# RPiLPC1114FDH28.net
KiCad netlist of a schematic drawn in EAGLE
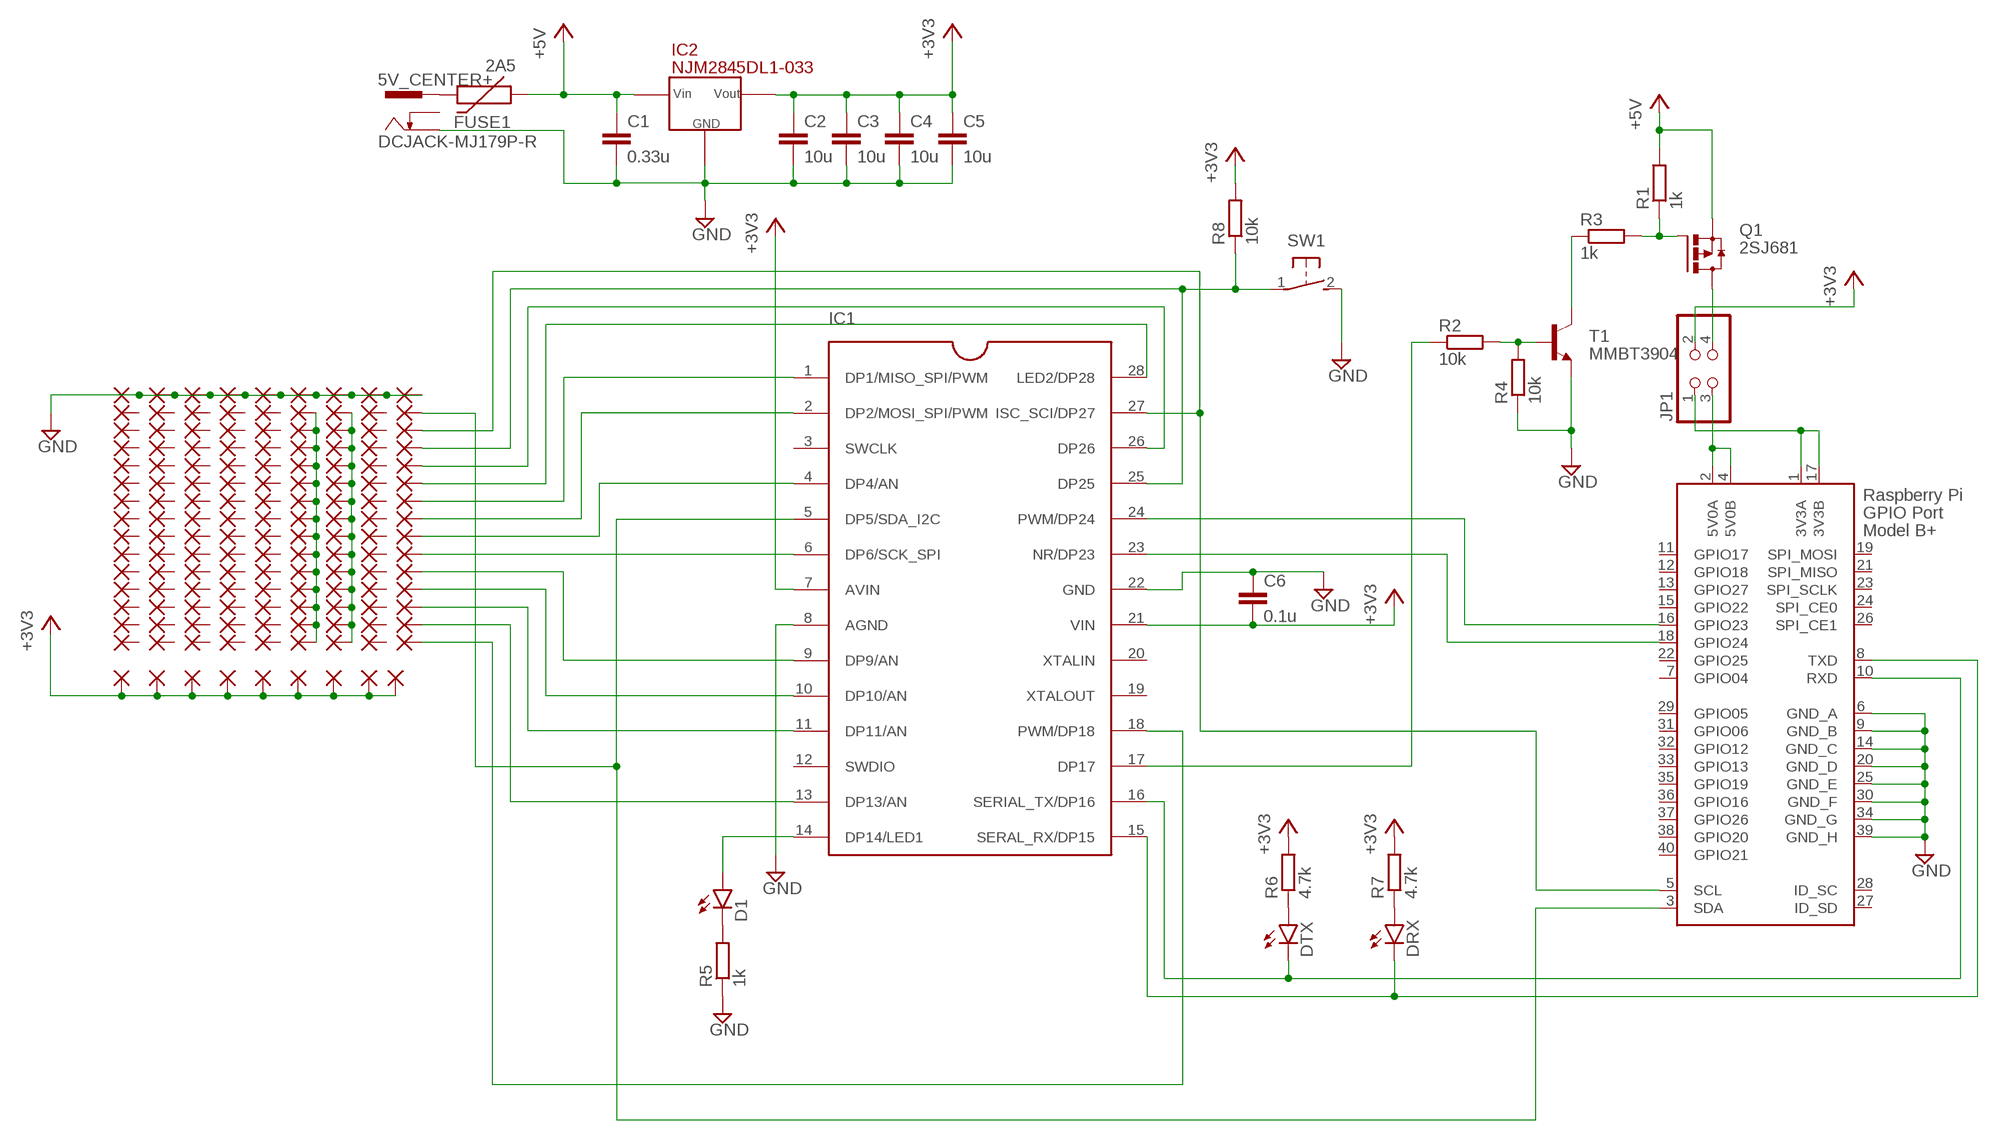
[diagram p0: schematic, sheet 1]

(export (version "E")
  (design (tool "Eeschema 10.0.6"))
  (components
    (comp (ref "5V_CENTER+")
      (value "DCJACK-MJ179P-R")
      (footprint "eagle-import:MJ-179P-R")
      (libsource (lib "eagle-import") (part "DCJACK-MJ179P-R"))
    )
    (comp (ref "C1")
      (value "0.33u")
      (footprint "eagle-import:C0603")
      (libsource (lib "eagle-import") (part "C-EUC0603"))
    )
    (comp (ref "C2")
      (value "10u")
      (footprint "eagle-import:C0805")
      (libsource (lib "eagle-import") (part "C-EUC0805"))
    )
    (comp (ref "C3")
      (value "10u")
      (footprint "eagle-import:C0805")
      (libsource (lib "eagle-import") (part "C-EUC0805"))
    )
    (comp (ref "C4")
      (value "10u")
      (footprint "eagle-import:C0805")
      (libsource (lib "eagle-import") (part "C-EUC0805"))
    )
    (comp (ref "C5")
      (value "10u")
      (footprint "eagle-import:C0805")
      (libsource (lib "eagle-import") (part "C-EUC0805"))
    )
    (comp (ref "C6")
      (value "0.1u")
      (footprint "eagle-import:C0603")
      (libsource (lib "eagle-import") (part "C-EUC0603"))
    )
    (comp (ref "D1")
      (value "LED0603")
      (footprint "eagle-import:LED-0603")
      (libsource (lib "eagle-import") (part "LED0603"))
    )
    (comp (ref "DRX")
      (value "LED0603")
      (footprint "eagle-import:LED-0603")
      (libsource (lib "eagle-import") (part "LED0603"))
    )
    (comp (ref "DTX")
      (value "LED0603")
      (footprint "eagle-import:LED-0603")
      (libsource (lib "eagle-import") (part "LED0603"))
    )
    (comp (ref "FUSE1")
      (value "2A5")
      (footprint "eagle-import:PTC")
      (libsource (lib "eagle-import") (part "PTCPTH"))
    )
    (comp (ref "IC1")
      (value "LPC1114DH28")
      (footprint "eagle-import:TSSOP28")
      (libsource (lib "eagle-import") (part "LPC1114DH28"))
    )
    (comp (ref "IC2")
      (value "NJM2845DL1-033")
      (footprint "eagle-import:TO-252-3")
      (libsource (lib "eagle-import") (part "NJM2845DL1"))
    )
    (comp (ref "JP1")
      (value "PINHD-2X2")
      (footprint "eagle-import:2X02")
      (libsource (lib "eagle-import") (part "PINHD-2X2"))
    )
    (comp (ref "PAD-3V3")
      (value "WIREPAD1,6/0,8")
      (footprint "eagle-import:1,6_0,8")
      (libsource (lib "eagle-import") (part "WIREPAD1,6/0,8"))
    )
    (comp (ref "PAD-DP1")
      (value "WIREPAD1,6/0,8")
      (footprint "eagle-import:1,6_0,8")
      (libsource (lib "eagle-import") (part "WIREPAD1,6/0,8"))
    )
    (comp (ref "PAD-DP2")
      (value "WIREPAD1,6/0,8")
      (footprint "eagle-import:1,6_0,8")
      (libsource (lib "eagle-import") (part "WIREPAD1,6/0,8"))
    )
    (comp (ref "PAD-DP4")
      (value "WIREPAD1,6/0,8")
      (footprint "eagle-import:1,6_0,8")
      (libsource (lib "eagle-import") (part "WIREPAD1,6/0,8"))
    )
    (comp (ref "PAD-DP5/SDA")
      (value "WIREPAD1,6/0,8")
      (footprint "eagle-import:1,6_0,8")
      (libsource (lib "eagle-import") (part "WIREPAD1,6/0,8"))
    )
    (comp (ref "PAD-DP6")
      (value "WIREPAD1,6/0,8")
      (footprint "eagle-import:1,6_0,8")
      (libsource (lib "eagle-import") (part "WIREPAD1,6/0,8"))
    )
    (comp (ref "PAD-DP9")
      (value "WIREPAD1,6/0,8")
      (footprint "eagle-import:1,6_0,8")
      (libsource (lib "eagle-import") (part "WIREPAD1,6/0,8"))
    )
    (comp (ref "PAD-DP10")
      (value "WIREPAD1,6/0,8")
      (footprint "eagle-import:1,6_0,8")
      (libsource (lib "eagle-import") (part "WIREPAD1,6/0,8"))
    )
    (comp (ref "PAD-DP11")
      (value "WIREPAD1,6/0,8")
      (footprint "eagle-import:1,6_0,8")
      (libsource (lib "eagle-import") (part "WIREPAD1,6/0,8"))
    )
    (comp (ref "PAD-DP13")
      (value "WIREPAD1,6/0,8")
      (footprint "eagle-import:1,6_0,8")
      (libsource (lib "eagle-import") (part "WIREPAD1,6/0,8"))
    )
    (comp (ref "PAD-DP18")
      (value "WIREPAD1,6/0,8")
      (footprint "eagle-import:1,6_0,8")
      (libsource (lib "eagle-import") (part "WIREPAD1,6/0,8"))
    )
    (comp (ref "PAD-DP25")
      (value "WIREPAD1,6/0,8")
      (footprint "eagle-import:1,6_0,8")
      (libsource (lib "eagle-import") (part "WIREPAD1,6/0,8"))
    )
    (comp (ref "PAD-DP26")
      (value "WIREPAD1,6/0,8")
      (footprint "eagle-import:1,6_0,8")
      (libsource (lib "eagle-import") (part "WIREPAD1,6/0,8"))
    )
    (comp (ref "PAD-DP27/SCL")
      (value "WIREPAD1,6/0,8")
      (footprint "eagle-import:1,6_0,8")
      (libsource (lib "eagle-import") (part "WIREPAD1,6/0,8"))
    )
    (comp (ref "PAD-DP28")
      (value "WIREPAD1,6/0,8")
      (footprint "eagle-import:1,6_0,8")
      (libsource (lib "eagle-import") (part "WIREPAD1,6/0,8"))
    )
    (comp (ref "PAD1")
      (value "WIREPAD1,6/0,8")
      (footprint "eagle-import:1,6_0,8")
      (libsource (lib "eagle-import") (part "WIREPAD1,6/0,8"))
    )
    (comp (ref "PAD2")
      (value "WIREPAD1,6/0,8")
      (footprint "eagle-import:1,6_0,8")
      (libsource (lib "eagle-import") (part "WIREPAD1,6/0,8"))
    )
    (comp (ref "PAD3")
      (value "WIREPAD1,6/0,8")
      (footprint "eagle-import:1,6_0,8")
      (libsource (lib "eagle-import") (part "WIREPAD1,6/0,8"))
    )
    (comp (ref "PAD4")
      (value "WIREPAD1,6/0,8")
      (footprint "eagle-import:1,6_0,8")
      (libsource (lib "eagle-import") (part "WIREPAD1,6/0,8"))
    )
    (comp (ref "PAD5")
      (value "WIREPAD1,6/0,8")
      (footprint "eagle-import:1,6_0,8")
      (libsource (lib "eagle-import") (part "WIREPAD1,6/0,8"))
    )
    (comp (ref "PAD6")
      (value "WIREPAD1,6/0,8")
      (footprint "eagle-import:1,6_0,8")
      (libsource (lib "eagle-import") (part "WIREPAD1,6/0,8"))
    )
    (comp (ref "PAD7")
      (value "WIREPAD1,6/0,8")
      (footprint "eagle-import:1,6_0,8")
      (libsource (lib "eagle-import") (part "WIREPAD1,6/0,8"))
    )
    (comp (ref "PAD8")
      (value "WIREPAD1,6/0,8")
      (footprint "eagle-import:1,6_0,8")
      (libsource (lib "eagle-import") (part "WIREPAD1,6/0,8"))
    )
    (comp (ref "PAD9")
      (value "WIREPAD1,6/0,8")
      (footprint "eagle-import:1,6_0,8")
      (libsource (lib "eagle-import") (part "WIREPAD1,6/0,8"))
    )
    (comp (ref "PAD10")
      (value "WIREPAD1,6/0,8")
      (footprint "eagle-import:1,6_0,8")
      (libsource (lib "eagle-import") (part "WIREPAD1,6/0,8"))
    )
    (comp (ref "PAD11")
      (value "WIREPAD1,6/0,8")
      (footprint "eagle-import:1,6_0,8")
      (libsource (lib "eagle-import") (part "WIREPAD1,6/0,8"))
    )
    (comp (ref "PAD12")
      (value "WIREPAD1,6/0,8")
      (footprint "eagle-import:1,6_0,8")
      (libsource (lib "eagle-import") (part "WIREPAD1,6/0,8"))
    )
    (comp (ref "PAD13")
      (value "WIREPAD1,6/0,8")
      (footprint "eagle-import:1,6_0,8")
      (libsource (lib "eagle-import") (part "WIREPAD1,6/0,8"))
    )
    (comp (ref "PAD14")
      (value "WIREPAD1,6/0,8")
      (footprint "eagle-import:1,6_0,8")
      (libsource (lib "eagle-import") (part "WIREPAD1,6/0,8"))
    )
    (comp (ref "PAD15")
      (value "WIREPAD1,6/0,8")
      (footprint "eagle-import:1,6_0,8")
      (libsource (lib "eagle-import") (part "WIREPAD1,6/0,8"))
    )
    (comp (ref "PAD16")
      (value "WIREPAD1,6/0,8")
      (footprint "eagle-import:1,6_0,8")
      (libsource (lib "eagle-import") (part "WIREPAD1,6/0,8"))
    )
    (comp (ref "PAD17")
      (value "WIREPAD1,6/0,8")
      (footprint "eagle-import:1,6_0,8")
      (libsource (lib "eagle-import") (part "WIREPAD1,6/0,8"))
    )
    (comp (ref "PAD18")
      (value "WIREPAD1,6/0,8")
      (footprint "eagle-import:1,6_0,8")
      (libsource (lib "eagle-import") (part "WIREPAD1,6/0,8"))
    )
    (comp (ref "PAD19")
      (value "WIREPAD1,6/0,8")
      (footprint "eagle-import:1,6_0,8")
      (libsource (lib "eagle-import") (part "WIREPAD1,6/0,8"))
    )
    (comp (ref "PAD20")
      (value "WIREPAD1,6/0,8")
      (footprint "eagle-import:1,6_0,8")
      (libsource (lib "eagle-import") (part "WIREPAD1,6/0,8"))
    )
    (comp (ref "PAD21")
      (value "WIREPAD1,6/0,8")
      (footprint "eagle-import:1,6_0,8")
      (libsource (lib "eagle-import") (part "WIREPAD1,6/0,8"))
    )
    (comp (ref "PAD22")
      (value "WIREPAD1,6/0,8")
      (footprint "eagle-import:1,6_0,8")
      (libsource (lib "eagle-import") (part "WIREPAD1,6/0,8"))
    )
    (comp (ref "PAD23")
      (value "WIREPAD1,6/0,8")
      (footprint "eagle-import:1,6_0,8")
      (libsource (lib "eagle-import") (part "WIREPAD1,6/0,8"))
    )
    (comp (ref "PAD24")
      (value "WIREPAD1,6/0,8")
      (footprint "eagle-import:1,6_0,8")
      (libsource (lib "eagle-import") (part "WIREPAD1,6/0,8"))
    )
    (comp (ref "PAD25")
      (value "WIREPAD1,6/0,8")
      (footprint "eagle-import:1,6_0,8")
      (libsource (lib "eagle-import") (part "WIREPAD1,6/0,8"))
    )
    (comp (ref "PAD26")
      (value "WIREPAD1,6/0,8")
      (footprint "eagle-import:1,6_0,8")
      (libsource (lib "eagle-import") (part "WIREPAD1,6/0,8"))
    )
    (comp (ref "PAD27")
      (value "WIREPAD1,6/0,8")
      (footprint "eagle-import:1,6_0,8")
      (libsource (lib "eagle-import") (part "WIREPAD1,6/0,8"))
    )
    (comp (ref "PAD28")
      (value "WIREPAD1,6/0,8")
      (footprint "eagle-import:1,6_0,8")
      (libsource (lib "eagle-import") (part "WIREPAD1,6/0,8"))
    )
    (comp (ref "PAD29")
      (value "WIREPAD1,6/0,8")
      (footprint "eagle-import:1,6_0,8")
      (libsource (lib "eagle-import") (part "WIREPAD1,6/0,8"))
    )
    (comp (ref "PAD30")
      (value "WIREPAD1,6/0,8")
      (footprint "eagle-import:1,6_0,8")
      (libsource (lib "eagle-import") (part "WIREPAD1,6/0,8"))
    )
    (comp (ref "PAD31")
      (value "WIREPAD1,6/0,8")
      (footprint "eagle-import:1,6_0,8")
      (libsource (lib "eagle-import") (part "WIREPAD1,6/0,8"))
    )
    (comp (ref "PAD32")
      (value "WIREPAD1,6/0,8")
      (footprint "eagle-import:1,6_0,8")
      (libsource (lib "eagle-import") (part "WIREPAD1,6/0,8"))
    )
    (comp (ref "PAD33")
      (value "WIREPAD1,6/0,8")
      (footprint "eagle-import:1,6_0,8")
      (libsource (lib "eagle-import") (part "WIREPAD1,6/0,8"))
    )
    (comp (ref "PAD34")
      (value "WIREPAD1,6/0,8")
      (footprint "eagle-import:1,6_0,8")
      (libsource (lib "eagle-import") (part "WIREPAD1,6/0,8"))
    )
    (comp (ref "PAD35")
      (value "WIREPAD1,6/0,8")
      (footprint "eagle-import:1,6_0,8")
      (libsource (lib "eagle-import") (part "WIREPAD1,6/0,8"))
    )
    (comp (ref "PAD36")
      (value "WIREPAD1,6/0,8")
      (footprint "eagle-import:1,6_0,8")
      (libsource (lib "eagle-import") (part "WIREPAD1,6/0,8"))
    )
    (comp (ref "PAD37")
      (value "WIREPAD1,6/0,8")
      (footprint "eagle-import:1,6_0,8")
      (libsource (lib "eagle-import") (part "WIREPAD1,6/0,8"))
    )
    (comp (ref "PAD38")
      (value "WIREPAD1,6/0,8")
      (footprint "eagle-import:1,6_0,8")
      (libsource (lib "eagle-import") (part "WIREPAD1,6/0,8"))
    )
    (comp (ref "PAD39")
      (value "WIREPAD1,6/0,8")
      (footprint "eagle-import:1,6_0,8")
      (libsource (lib "eagle-import") (part "WIREPAD1,6/0,8"))
    )
    (comp (ref "PAD40")
      (value "WIREPAD1,6/0,8")
      (footprint "eagle-import:1,6_0,8")
      (libsource (lib "eagle-import") (part "WIREPAD1,6/0,8"))
    )
    (comp (ref "PAD41")
      (value "WIREPAD1,6/0,8")
      (footprint "eagle-import:1,6_0,8")
      (libsource (lib "eagle-import") (part "WIREPAD1,6/0,8"))
    )
    (comp (ref "PAD42")
      (value "WIREPAD1,6/0,8")
      (footprint "eagle-import:1,6_0,8")
      (libsource (lib "eagle-import") (part "WIREPAD1,6/0,8"))
    )
    (comp (ref "PAD43")
      (value "WIREPAD1,6/0,8")
      (footprint "eagle-import:1,6_0,8")
      (libsource (lib "eagle-import") (part "WIREPAD1,6/0,8"))
    )
    (comp (ref "PAD44")
      (value "WIREPAD1,6/0,8")
      (footprint "eagle-import:1,6_0,8")
      (libsource (lib "eagle-import") (part "WIREPAD1,6/0,8"))
    )
    (comp (ref "PAD45")
      (value "WIREPAD1,6/0,8")
      (footprint "eagle-import:1,6_0,8")
      (libsource (lib "eagle-import") (part "WIREPAD1,6/0,8"))
    )
    (comp (ref "PAD46")
      (value "WIREPAD1,6/0,8")
      (footprint "eagle-import:1,6_0,8")
      (libsource (lib "eagle-import") (part "WIREPAD1,6/0,8"))
    )
    (comp (ref "PAD47")
      (value "WIREPAD1,6/0,8")
      (footprint "eagle-import:1,6_0,8")
      (libsource (lib "eagle-import") (part "WIREPAD1,6/0,8"))
    )
    (comp (ref "PAD48")
      (value "WIREPAD1,6/0,8")
      (footprint "eagle-import:1,6_0,8")
      (libsource (lib "eagle-import") (part "WIREPAD1,6/0,8"))
    )
    (comp (ref "PAD49")
      (value "WIREPAD1,6/0,8")
      (footprint "eagle-import:1,6_0,8")
      (libsource (lib "eagle-import") (part "WIREPAD1,6/0,8"))
    )
    (comp (ref "PAD50")
      (value "WIREPAD1,6/0,8")
      (footprint "eagle-import:1,6_0,8")
      (libsource (lib "eagle-import") (part "WIREPAD1,6/0,8"))
    )
    (comp (ref "PAD51")
      (value "WIREPAD1,6/0,8")
      (footprint "eagle-import:1,6_0,8")
      (libsource (lib "eagle-import") (part "WIREPAD1,6/0,8"))
    )
    (comp (ref "PAD53")
      (value "WIREPAD1,6/0,8")
      (footprint "eagle-import:1,6_0,8")
      (libsource (lib "eagle-import") (part "WIREPAD1,6/0,8"))
    )
    (comp (ref "PAD54")
      (value "WIREPAD1,6/0,8")
      (footprint "eagle-import:1,6_0,8")
      (libsource (lib "eagle-import") (part "WIREPAD1,6/0,8"))
    )
    (comp (ref "PAD55")
      (value "WIREPAD1,6/0,8")
      (footprint "eagle-import:1,6_0,8")
      (libsource (lib "eagle-import") (part "WIREPAD1,6/0,8"))
    )
    (comp (ref "PAD56")
      (value "WIREPAD1,6/0,8")
      (footprint "eagle-import:1,6_0,8")
      (libsource (lib "eagle-import") (part "WIREPAD1,6/0,8"))
    )
    (comp (ref "PAD57")
      (value "WIREPAD1,6/0,8")
      (footprint "eagle-import:1,6_0,8")
      (libsource (lib "eagle-import") (part "WIREPAD1,6/0,8"))
    )
    (comp (ref "PAD58")
      (value "WIREPAD1,6/0,8")
      (footprint "eagle-import:1,6_0,8")
      (libsource (lib "eagle-import") (part "WIREPAD1,6/0,8"))
    )
    (comp (ref "PAD59")
      (value "WIREPAD1,6/0,8")
      (footprint "eagle-import:1,6_0,8")
      (libsource (lib "eagle-import") (part "WIREPAD1,6/0,8"))
    )
    (comp (ref "PAD60")
      (value "WIREPAD1,6/0,8")
      (footprint "eagle-import:1,6_0,8")
      (libsource (lib "eagle-import") (part "WIREPAD1,6/0,8"))
    )
    (comp (ref "PAD61")
      (value "WIREPAD1,6/0,8")
      (footprint "eagle-import:1,6_0,8")
      (libsource (lib "eagle-import") (part "WIREPAD1,6/0,8"))
    )
    (comp (ref "PAD62")
      (value "WIREPAD1,6/0,8")
      (footprint "eagle-import:1,6_0,8")
      (libsource (lib "eagle-import") (part "WIREPAD1,6/0,8"))
    )
    (comp (ref "PAD63")
      (value "WIREPAD1,6/0,8")
      (footprint "eagle-import:1,6_0,8")
      (libsource (lib "eagle-import") (part "WIREPAD1,6/0,8"))
    )
    (comp (ref "PAD64")
      (value "WIREPAD1,6/0,8")
      (footprint "eagle-import:1,6_0,8")
      (libsource (lib "eagle-import") (part "WIREPAD1,6/0,8"))
    )
    (comp (ref "PAD65")
      (value "WIREPAD1,6/0,8")
      (footprint "eagle-import:1,6_0,8")
      (libsource (lib "eagle-import") (part "WIREPAD1,6/0,8"))
    )
    (comp (ref "PAD66")
      (value "WIREPAD1,6/0,8")
      (footprint "eagle-import:1,6_0,8")
      (libsource (lib "eagle-import") (part "WIREPAD1,6/0,8"))
    )
    (comp (ref "PAD67")
      (value "WIREPAD1,6/0,8")
      (footprint "eagle-import:1,6_0,8")
      (libsource (lib "eagle-import") (part "WIREPAD1,6/0,8"))
    )
    (comp (ref "PAD69")
      (value "WIREPAD1,6/0,8")
      (footprint "eagle-import:1,6_0,8")
      (libsource (lib "eagle-import") (part "WIREPAD1,6/0,8"))
    )
    (comp (ref "PAD70")
      (value "WIREPAD1,6/0,8")
      (footprint "eagle-import:1,6_0,8")
      (libsource (lib "eagle-import") (part "WIREPAD1,6/0,8"))
    )
    (comp (ref "PAD71")
      (value "WIREPAD1,6/0,8")
      (footprint "eagle-import:1,6_0,8")
      (libsource (lib "eagle-import") (part "WIREPAD1,6/0,8"))
    )
    (comp (ref "PAD72")
      (value "WIREPAD1,6/0,8")
      (footprint "eagle-import:1,6_0,8")
      (libsource (lib "eagle-import") (part "WIREPAD1,6/0,8"))
    )
    (comp (ref "PAD73")
      (value "WIREPAD1,6/0,8")
      (footprint "eagle-import:1,6_0,8")
      (libsource (lib "eagle-import") (part "WIREPAD1,6/0,8"))
    )
    (comp (ref "PAD74")
      (value "WIREPAD1,6/0,8")
      (footprint "eagle-import:1,6_0,8")
      (libsource (lib "eagle-import") (part "WIREPAD1,6/0,8"))
    )
    (comp (ref "PAD75")
      (value "WIREPAD1,6/0,8")
      (footprint "eagle-import:1,6_0,8")
      (libsource (lib "eagle-import") (part "WIREPAD1,6/0,8"))
    )
    (comp (ref "PAD76")
      (value "WIREPAD1,6/0,8")
      (footprint "eagle-import:1,6_0,8")
      (libsource (lib "eagle-import") (part "WIREPAD1,6/0,8"))
    )
    (comp (ref "PAD77")
      (value "WIREPAD1,6/0,8")
      (footprint "eagle-import:1,6_0,8")
      (libsource (lib "eagle-import") (part "WIREPAD1,6/0,8"))
    )
    (comp (ref "PAD78")
      (value "WIREPAD1,6/0,8")
      (footprint "eagle-import:1,6_0,8")
      (libsource (lib "eagle-import") (part "WIREPAD1,6/0,8"))
    )
    (comp (ref "PAD79")
      (value "WIREPAD1,6/0,8")
      (footprint "eagle-import:1,6_0,8")
      (libsource (lib "eagle-import") (part "WIREPAD1,6/0,8"))
    )
    (comp (ref "PAD80")
      (value "WIREPAD1,6/0,8")
      (footprint "eagle-import:1,6_0,8")
      (libsource (lib "eagle-import") (part "WIREPAD1,6/0,8"))
    )
    (comp (ref "PAD81")
      (value "WIREPAD1,6/0,8")
      (footprint "eagle-import:1,6_0,8")
      (libsource (lib "eagle-import") (part "WIREPAD1,6/0,8"))
    )
    (comp (ref "PAD82")
      (value "WIREPAD1,6/0,8")
      (footprint "eagle-import:1,6_0,8")
      (libsource (lib "eagle-import") (part "WIREPAD1,6/0,8"))
    )
    (comp (ref "PAD83")
      (value "WIREPAD1,6/0,8")
      (footprint "eagle-import:1,6_0,8")
      (libsource (lib "eagle-import") (part "WIREPAD1,6/0,8"))
    )
    (comp (ref "PAD100")
      (value "WIREPAD1,6/0,8")
      (footprint "eagle-import:1,6_0,8")
      (libsource (lib "eagle-import") (part "WIREPAD1,6/0,8"))
    )
    (comp (ref "PAD101")
      (value "WIREPAD1,6/0,8")
      (footprint "eagle-import:1,6_0,8")
      (libsource (lib "eagle-import") (part "WIREPAD1,6/0,8"))
    )
    (comp (ref "PAD102")
      (value "WIREPAD1,6/0,8")
      (footprint "eagle-import:1,6_0,8")
      (libsource (lib "eagle-import") (part "WIREPAD1,6/0,8"))
    )
    (comp (ref "PAD103")
      (value "WIREPAD1,6/0,8")
      (footprint "eagle-import:1,6_0,8")
      (libsource (lib "eagle-import") (part "WIREPAD1,6/0,8"))
    )
    (comp (ref "PAD104")
      (value "WIREPAD1,6/0,8")
      (footprint "eagle-import:1,6_0,8")
      (libsource (lib "eagle-import") (part "WIREPAD1,6/0,8"))
    )
    (comp (ref "PAD105")
      (value "WIREPAD1,6/0,8")
      (footprint "eagle-import:1,6_0,8")
      (libsource (lib "eagle-import") (part "WIREPAD1,6/0,8"))
    )
    (comp (ref "PAD106")
      (value "WIREPAD1,6/0,8")
      (footprint "eagle-import:1,6_0,8")
      (libsource (lib "eagle-import") (part "WIREPAD1,6/0,8"))
    )
    (comp (ref "PAD107")
      (value "WIREPAD1,6/0,8")
      (footprint "eagle-import:1,6_0,8")
      (libsource (lib "eagle-import") (part "WIREPAD1,6/0,8"))
    )
    (comp (ref "PAD108")
      (value "WIREPAD1,6/0,8")
      (footprint "eagle-import:1,6_0,8")
      (libsource (lib "eagle-import") (part "WIREPAD1,6/0,8"))
    )
    (comp (ref "PAD109")
      (value "WIREPAD1,6/0,8")
      (footprint "eagle-import:1,6_0,8")
      (libsource (lib "eagle-import") (part "WIREPAD1,6/0,8"))
    )
    (comp (ref "PAD110")
      (value "WIREPAD1,6/0,8")
      (footprint "eagle-import:1,6_0,8")
      (libsource (lib "eagle-import") (part "WIREPAD1,6/0,8"))
    )
    (comp (ref "PAD112")
      (value "WIREPAD1,6/0,8")
      (footprint "eagle-import:1,6_0,8")
      (libsource (lib "eagle-import") (part "WIREPAD1,6/0,8"))
    )
    (comp (ref "PAD113")
      (value "WIREPAD1,6/0,8")
      (footprint "eagle-import:1,6_0,8")
      (libsource (lib "eagle-import") (part "WIREPAD1,6/0,8"))
    )
    (comp (ref "PAD114")
      (value "WIREPAD1,6/0,8")
      (footprint "eagle-import:1,6_0,8")
      (libsource (lib "eagle-import") (part "WIREPAD1,6/0,8"))
    )
    (comp (ref "PAD115")
      (value "WIREPAD1,6/0,8")
      (footprint "eagle-import:1,6_0,8")
      (libsource (lib "eagle-import") (part "WIREPAD1,6/0,8"))
    )
    (comp (ref "PAD117")
      (value "WIREPAD1,6/0,8")
      (footprint "eagle-import:1,6_0,8")
      (libsource (lib "eagle-import") (part "WIREPAD1,6/0,8"))
    )
    (comp (ref "PAD118")
      (value "WIREPAD1,6/0,8")
      (footprint "eagle-import:1,6_0,8")
      (libsource (lib "eagle-import") (part "WIREPAD1,6/0,8"))
    )
    (comp (ref "PAD119")
      (value "WIREPAD1,6/0,8")
      (footprint "eagle-import:1,6_0,8")
      (libsource (lib "eagle-import") (part "WIREPAD1,6/0,8"))
    )
    (comp (ref "PAD120")
      (value "WIREPAD1,6/0,8")
      (footprint "eagle-import:1,6_0,8")
      (libsource (lib "eagle-import") (part "WIREPAD1,6/0,8"))
    )
    (comp (ref "PAD121")
      (value "WIREPAD1,6/0,8")
      (footprint "eagle-import:1,6_0,8")
      (libsource (lib "eagle-import") (part "WIREPAD1,6/0,8"))
    )
    (comp (ref "PAD122")
      (value "WIREPAD1,6/0,8")
      (footprint "eagle-import:1,6_0,8")
      (libsource (lib "eagle-import") (part "WIREPAD1,6/0,8"))
    )
    (comp (ref "PAD123")
      (value "WIREPAD1,6/0,8")
      (footprint "eagle-import:1,6_0,8")
      (libsource (lib "eagle-import") (part "WIREPAD1,6/0,8"))
    )
    (comp (ref "PAD124")
      (value "WIREPAD1,6/0,8")
      (footprint "eagle-import:1,6_0,8")
      (libsource (lib "eagle-import") (part "WIREPAD1,6/0,8"))
    )
    (comp (ref "PAD126")
      (value "WIREPAD1,6/0,8")
      (footprint "eagle-import:1,6_0,8")
      (libsource (lib "eagle-import") (part "WIREPAD1,6/0,8"))
    )
    (comp (ref "PAD127")
      (value "WIREPAD1,6/0,8")
      (footprint "eagle-import:1,6_0,8")
      (libsource (lib "eagle-import") (part "WIREPAD1,6/0,8"))
    )
    (comp (ref "PAD128")
      (value "WIREPAD1,6/0,8")
      (footprint "eagle-import:1,6_0,8")
      (libsource (lib "eagle-import") (part "WIREPAD1,6/0,8"))
    )
    (comp (ref "PAD129")
      (value "WIREPAD1,6/0,8")
      (footprint "eagle-import:1,6_0,8")
      (libsource (lib "eagle-import") (part "WIREPAD1,6/0,8"))
    )
    (comp (ref "PAD130")
      (value "WIREPAD1,6/0,8")
      (footprint "eagle-import:1,6_0,8")
      (libsource (lib "eagle-import") (part "WIREPAD1,6/0,8"))
    )
    (comp (ref "PAD131")
      (value "WIREPAD1,6/0,8")
      (footprint "eagle-import:1,6_0,8")
      (libsource (lib "eagle-import") (part "WIREPAD1,6/0,8"))
    )
    (comp (ref "PAD133")
      (value "WIREPAD1,6/0,8")
      (footprint "eagle-import:1,6_0,8")
      (libsource (lib "eagle-import") (part "WIREPAD1,6/0,8"))
    )
    (comp (ref "PAD134")
      (value "WIREPAD1,6/0,8")
      (footprint "eagle-import:1,6_0,8")
      (libsource (lib "eagle-import") (part "WIREPAD1,6/0,8"))
    )
    (comp (ref "PAD135")
      (value "WIREPAD1,6/0,8")
      (footprint "eagle-import:1,6_0,8")
      (libsource (lib "eagle-import") (part "WIREPAD1,6/0,8"))
    )
    (comp (ref "PAD136")
      (value "WIREPAD1,6/0,8")
      (footprint "eagle-import:1,6_0,8")
      (libsource (lib "eagle-import") (part "WIREPAD1,6/0,8"))
    )
    (comp (ref "PAD137")
      (value "WIREPAD1,6/0,8")
      (footprint "eagle-import:1,6_0,8")
      (libsource (lib "eagle-import") (part "WIREPAD1,6/0,8"))
    )
    (comp (ref "PAD138")
      (value "WIREPAD1,6/0,8")
      (footprint "eagle-import:1,6_0,8")
      (libsource (lib "eagle-import") (part "WIREPAD1,6/0,8"))
    )
    (comp (ref "PAD140")
      (value "WIREPAD1,6/0,8")
      (footprint "eagle-import:1,6_0,8")
      (libsource (lib "eagle-import") (part "WIREPAD1,6/0,8"))
    )
    (comp (ref "PAD141")
      (value "WIREPAD1,6/0,8")
      (footprint "eagle-import:1,6_0,8")
      (libsource (lib "eagle-import") (part "WIREPAD1,6/0,8"))
    )
    (comp (ref "PAD142")
      (value "WIREPAD1,6/0,8")
      (footprint "eagle-import:1,6_0,8")
      (libsource (lib "eagle-import") (part "WIREPAD1,6/0,8"))
    )
    (comp (ref "PAD143")
      (value "WIREPAD1,6/0,8")
      (footprint "eagle-import:1,6_0,8")
      (libsource (lib "eagle-import") (part "WIREPAD1,6/0,8"))
    )
    (comp (ref "PAD144")
      (value "WIREPAD1,6/0,8")
      (footprint "eagle-import:1,6_0,8")
      (libsource (lib "eagle-import") (part "WIREPAD1,6/0,8"))
    )
    (comp (ref "PAD145")
      (value "WIREPAD1,6/0,8")
      (footprint "eagle-import:1,6_0,8")
      (libsource (lib "eagle-import") (part "WIREPAD1,6/0,8"))
    )
    (comp (ref "PAD147")
      (value "WIREPAD1,6/0,8")
      (footprint "eagle-import:1,6_0,8")
      (libsource (lib "eagle-import") (part "WIREPAD1,6/0,8"))
    )
    (comp (ref "PAD148")
      (value "WIREPAD1,6/0,8")
      (footprint "eagle-import:1,6_0,8")
      (libsource (lib "eagle-import") (part "WIREPAD1,6/0,8"))
    )
    (comp (ref "PAD149")
      (value "WIREPAD1,6/0,8")
      (footprint "eagle-import:1,6_0,8")
      (libsource (lib "eagle-import") (part "WIREPAD1,6/0,8"))
    )
    (comp (ref "PAD150")
      (value "WIREPAD1,6/0,8")
      (footprint "eagle-import:1,6_0,8")
      (libsource (lib "eagle-import") (part "WIREPAD1,6/0,8"))
    )
    (comp (ref "PAD151")
      (value "WIREPAD1,6/0,8")
      (footprint "eagle-import:1,6_0,8")
      (libsource (lib "eagle-import") (part "WIREPAD1,6/0,8"))
    )
    (comp (ref "PAD152")
      (value "WIREPAD1,6/0,8")
      (footprint "eagle-import:1,6_0,8")
      (libsource (lib "eagle-import") (part "WIREPAD1,6/0,8"))
    )
    (comp (ref "PAD_GND")
      (value "WIREPAD1,6/0,8")
      (footprint "eagle-import:1,6_0,8")
      (libsource (lib "eagle-import") (part "WIREPAD1,6/0,8"))
    )
    (comp (ref "Q1")
      (value "2SJ681")
      (footprint "eagle-import:2-7J2B(TOSHIBA)")
      (libsource (lib "eagle-import") (part "2SJ681"))
    )
    (comp (ref "R1")
      (value "1k")
      (footprint "eagle-import:R0603")
      (libsource (lib "eagle-import") (part "R-EU_R0603"))
    )
    (comp (ref "R2")
      (value "10k")
      (footprint "eagle-import:R0603")
      (libsource (lib "eagle-import") (part "R-EU_R0603"))
    )
    (comp (ref "R3")
      (value "1k")
      (footprint "eagle-import:R0603")
      (libsource (lib "eagle-import") (part "R-EU_R0603"))
    )
    (comp (ref "R4")
      (value "10k")
      (footprint "eagle-import:R0603")
      (libsource (lib "eagle-import") (part "R-EU_R0603"))
    )
    (comp (ref "R5")
      (value "1k")
      (footprint "eagle-import:R0603")
      (libsource (lib "eagle-import") (part "R-EU_R0603"))
    )
    (comp (ref "R6")
      (value "4.7k")
      (footprint "eagle-import:R0603")
      (libsource (lib "eagle-import") (part "R-EU_R0603"))
    )
    (comp (ref "R7")
      (value "4.7k")
      (footprint "eagle-import:R0603")
      (libsource (lib "eagle-import") (part "R-EU_R0603"))
    )
    (comp (ref "R8")
      (value "10k")
      (footprint "eagle-import:R0603")
      (libsource (lib "eagle-import") (part "R-EU_R0603"))
    )
    (comp (ref "SW1")
      (value "SWITCH-TACTILESW")
      (footprint "eagle-import:SWITCH-TACTILE")
      (libsource (lib "eagle-import") (part "SWITCH-TACTILESW"))
    )
    (comp (ref "T1")
      (value "MMBT3904")
      (footprint "eagle-import:SOT23-3")
      (libsource (lib "eagle-import") (part "TRANSISTOR_NPNMMBT2222A"))
    )
    (comp (ref "X1")
      (value "RASPI_GPIO_B+#_PIN")
      (footprint "eagle-import:RASPI_GPIO_B+_PIN")
      (libsource (lib "eagle-import") (part "RASPI_GPIO_B+#_PIN"))
    )
  )
  (nets
    (net (code "1") (name "+3V3") (class "Default")
      (node (ref "C2") (pin "1") (pinfunction "1_1") (pintype "passive"))
      (node (ref "C3") (pin "1") (pinfunction "1_1") (pintype "passive"))
      (node (ref "C4") (pin "1") (pinfunction "1_1") (pintype "passive"))
      (node (ref "C5") (pin "1") (pinfunction "1_1") (pintype "passive"))
      (node (ref "C6") (pin "2") (pinfunction "2_2") (pintype "passive"))
      (node (ref "IC1") (pin "21") (pinfunction "VIN_21") (pintype "power_in"))
      (node (ref "IC1") (pin "7") (pinfunction "AVIN_7") (pintype "power_in"))
      (node (ref "IC2") (pin "VOUT") (pinfunction "VOUT_VOUT") (pintype "power_in"))
      (node (ref "JP1") (pin "2") (pinfunction "2_2") (pintype "passive"))
      (node (ref "PAD-3V3") (pin "1") (pinfunction "P_1") (pintype "passive"))
      (node (ref "PAD117") (pin "1") (pinfunction "P_1") (pintype "passive"))
      (node (ref "PAD118") (pin "1") (pinfunction "P_1") (pintype "passive"))
      (node (ref "PAD119") (pin "1") (pinfunction "P_1") (pintype "passive"))
      (node (ref "PAD120") (pin "1") (pinfunction "P_1") (pintype "passive"))
      (node (ref "PAD121") (pin "1") (pinfunction "P_1") (pintype "passive"))
      (node (ref "PAD122") (pin "1") (pinfunction "P_1") (pintype "passive"))
      (node (ref "PAD123") (pin "1") (pinfunction "P_1") (pintype "passive"))
      (node (ref "PAD124") (pin "1") (pinfunction "P_1") (pintype "passive"))
      (node (ref "R6") (pin "2") (pinfunction "2_2") (pintype "passive"))
      (node (ref "R7") (pin "2") (pinfunction "2_2") (pintype "passive"))
      (node (ref "R8") (pin "2") (pinfunction "2_2") (pintype "passive"))
    )
    (net (code "2") (name "+5V") (class "Default")
      (node (ref "C1") (pin "1") (pinfunction "1_1") (pintype "passive"))
      (node (ref "FUSE1") (pin "P$1") (pinfunction "1_P$1") (pintype "bidirectional"))
      (node (ref "IC2") (pin "VIN") (pinfunction "VIN_VIN") (pintype "power_in"))
      (node (ref "Q1") (pin "P$3") (pinfunction "S_P$3") (pintype "passive"))
      (node (ref "R1") (pin "2") (pinfunction "2_2") (pintype "passive"))
    )
    (net (code "3") (name "GND") (class "Default")
      (node (ref "5V_CENTER+") (pin "2") (pinfunction "2_2") (pintype "passive"))
      (node (ref "C1") (pin "2") (pinfunction "2_2") (pintype "passive"))
      (node (ref "C2") (pin "2") (pinfunction "2_2") (pintype "passive"))
      (node (ref "C3") (pin "2") (pinfunction "2_2") (pintype "passive"))
      (node (ref "C4") (pin "2") (pinfunction "2_2") (pintype "passive"))
      (node (ref "C5") (pin "2") (pinfunction "2_2") (pintype "passive"))
      (node (ref "C6") (pin "1") (pinfunction "1_1") (pintype "passive"))
      (node (ref "IC1") (pin "22") (pinfunction "GND_22") (pintype "power_in"))
      (node (ref "IC1") (pin "8") (pinfunction "AGND_8") (pintype "power_in"))
      (node (ref "IC2") (pin "GND") (pinfunction "GND_GND") (pintype "power_in"))
      (node (ref "PAD1") (pin "1") (pinfunction "P_1") (pintype "passive"))
      (node (ref "PAD10") (pin "1") (pinfunction "P_1") (pintype "passive"))
      (node (ref "PAD100") (pin "1") (pinfunction "P_1") (pintype "passive"))
      (node (ref "PAD19") (pin "1") (pinfunction "P_1") (pintype "passive"))
      (node (ref "PAD28") (pin "1") (pinfunction "P_1") (pintype "passive"))
      (node (ref "PAD37") (pin "1") (pinfunction "P_1") (pintype "passive"))
      (node (ref "PAD53") (pin "1") (pinfunction "P_1") (pintype "passive"))
      (node (ref "PAD69") (pin "1") (pinfunction "P_1") (pintype "passive"))
      (node (ref "PAD_GND") (pin "1") (pinfunction "P_1") (pintype "passive"))
      (node (ref "R4") (pin "1") (pinfunction "1_1") (pintype "passive"))
      (node (ref "R5") (pin "1") (pinfunction "1_1") (pintype "passive"))
      (node (ref "SW1") (pin "2") (pinfunction "2_2") (pintype "passive"))
      (node (ref "T1") (pin "2") (pinfunction "E_2") (pintype "passive"))
      (node (ref "X1") (pin "14") (pinfunction "GND_C_14") (pintype "power_in"))
      (node (ref "X1") (pin "20") (pinfunction "GND_D_20") (pintype "power_in"))
      (node (ref "X1") (pin "25") (pinfunction "GND_E_25") (pintype "power_in"))
      (node (ref "X1") (pin "30") (pinfunction "GND_F_30") (pintype "power_in"))
      (node (ref "X1") (pin "34") (pinfunction "GND_G_34") (pintype "power_in"))
      (node (ref "X1") (pin "39") (pinfunction "GND_H_39") (pintype "power_in"))
      (node (ref "X1") (pin "6") (pinfunction "GND_A_6") (pintype "power_in"))
      (node (ref "X1") (pin "9") (pinfunction "GND_B_9") (pintype "power_in"))
    )
    (net (code "4") (name "Net-(D1-PadC)") (class "Default")
      (node (ref "D1") (pin "C") (pinfunction "C_C") (pintype "passive"))
      (node (ref "R5") (pin "2") (pinfunction "2_2") (pintype "passive"))
    )
    (net (code "5") (name "Net-(DRX-PadA)") (class "Default")
      (node (ref "DRX") (pin "A") (pinfunction "A_A") (pintype "passive"))
      (node (ref "R7") (pin "1") (pinfunction "1_1") (pintype "passive"))
    )
    (net (code "6") (name "Net-(DTX-PadA)") (class "Default")
      (node (ref "DTX") (pin "A") (pinfunction "A_A") (pintype "passive"))
      (node (ref "R6") (pin "1") (pinfunction "1_1") (pintype "passive"))
    )
    (net (code "7") (name "Net-(FUSE1-2)") (class "Default")
      (node (ref "5V_CENTER+") (pin "1") (pinfunction "1_1") (pintype "passive"))
      (node (ref "FUSE1") (pin "P$2") (pinfunction "2_P$2") (pintype "bidirectional"))
    )
    (net (code "8") (name "Net-(IC1-DP1{slash}MISO_SPI{slash}PWM)") (class "Default")
      (node (ref "IC1") (pin "1") (pinfunction "DP1/MISO_SPI/PWM_1") (pintype "bidirectional"))
      (node (ref "PAD-DP1") (pin "1") (pinfunction "P_1") (pintype "passive"))
    )
    (net (code "9") (name "Net-(IC1-DP2{slash}MOSI_SPI{slash}PWM)") (class "Default")
      (node (ref "IC1") (pin "2") (pinfunction "DP2/MOSI_SPI/PWM_2") (pintype "bidirectional"))
      (node (ref "PAD-DP2") (pin "1") (pinfunction "P_1") (pintype "passive"))
    )
    (net (code "10") (name "Net-(IC1-DP4{slash}AN)") (class "Default")
      (node (ref "IC1") (pin "4") (pinfunction "DP4/AN_4") (pintype "bidirectional"))
      (node (ref "PAD-DP4") (pin "1") (pinfunction "P_1") (pintype "passive"))
    )
    (net (code "11") (name "Net-(IC1-DP5{slash}SDA_I2C)") (class "Default")
      (node (ref "IC1") (pin "5") (pinfunction "DP5/SDA_I2C_5") (pintype "bidirectional"))
      (node (ref "PAD-DP5/SDA") (pin "1") (pinfunction "P_1") (pintype "passive"))
      (node (ref "X1") (pin "3") (pinfunction "SDA_3") (pintype "bidirectional"))
    )
    (net (code "12") (name "Net-(IC1-DP6{slash}SCK_SPI)") (class "Default")
      (node (ref "IC1") (pin "6") (pinfunction "DP6/SCK_SPI_6") (pintype "bidirectional"))
      (node (ref "PAD-DP6") (pin "1") (pinfunction "P_1") (pintype "passive"))
    )
    (net (code "13") (name "Net-(IC1-DP9{slash}AN)") (class "Default")
      (node (ref "IC1") (pin "9") (pinfunction "DP9/AN_9") (pintype "bidirectional"))
      (node (ref "PAD-DP9") (pin "1") (pinfunction "P_1") (pintype "passive"))
    )
    (net (code "14") (name "Net-(IC1-DP10{slash}AN)") (class "Default")
      (node (ref "IC1") (pin "10") (pinfunction "DP10/AN_10") (pintype "bidirectional"))
      (node (ref "PAD-DP10") (pin "1") (pinfunction "P_1") (pintype "passive"))
    )
    (net (code "15") (name "Net-(IC1-DP11{slash}AN)") (class "Default")
      (node (ref "IC1") (pin "11") (pinfunction "DP11/AN_11") (pintype "bidirectional"))
      (node (ref "PAD-DP11") (pin "1") (pinfunction "P_1") (pintype "passive"))
    )
    (net (code "16") (name "Net-(IC1-DP13{slash}AN)") (class "Default")
      (node (ref "IC1") (pin "13") (pinfunction "DP13/AN_13") (pintype "bidirectional"))
      (node (ref "PAD-DP13") (pin "1") (pinfunction "P_1") (pintype "passive"))
    )
    (net (code "17") (name "Net-(IC1-DP14{slash}LED1)") (class "Default")
      (node (ref "D1") (pin "A") (pinfunction "A_A") (pintype "passive"))
      (node (ref "IC1") (pin "14") (pinfunction "DP14/LED1_14") (pintype "bidirectional"))
    )
    (net (code "18") (name "Net-(IC1-DP17)") (class "Default")
      (node (ref "IC1") (pin "17") (pinfunction "DP17_17") (pintype "bidirectional"))
      (node (ref "R2") (pin "1") (pinfunction "1_1") (pintype "passive"))
    )
    (net (code "19") (name "Net-(IC1-DP25)") (class "Default")
      (node (ref "IC1") (pin "25") (pinfunction "DP25_25") (pintype "bidirectional"))
      (node (ref "PAD-DP25") (pin "1") (pinfunction "P_1") (pintype "passive"))
      (node (ref "R8") (pin "1") (pinfunction "1_1") (pintype "passive"))
      (node (ref "SW1") (pin "1") (pinfunction "1_1") (pintype "passive"))
    )
    (net (code "20") (name "Net-(IC1-DP26)") (class "Default")
      (node (ref "IC1") (pin "26") (pinfunction "DP26_26") (pintype "bidirectional"))
      (node (ref "PAD-DP26") (pin "1") (pinfunction "P_1") (pintype "passive"))
    )
    (net (code "21") (name "Net-(IC1-ISC_SCI{slash}DP27)") (class "Default")
      (node (ref "IC1") (pin "27") (pinfunction "ISC_SCI/DP27_27") (pintype "bidirectional"))
      (node (ref "PAD-DP27/SCL") (pin "1") (pinfunction "P_1") (pintype "passive"))
      (node (ref "X1") (pin "5") (pinfunction "SCL_5") (pintype "bidirectional"))
    )
    (net (code "22") (name "Net-(IC1-LED2{slash}DP28)") (class "Default")
      (node (ref "IC1") (pin "28") (pinfunction "LED2/DP28_28") (pintype "bidirectional"))
      (node (ref "PAD-DP28") (pin "1") (pinfunction "P_1") (pintype "passive"))
    )
    (net (code "23") (name "Net-(IC1-NR{slash}DP23)") (class "Default")
      (node (ref "IC1") (pin "23") (pinfunction "NR/DP23_23") (pintype "bidirectional"))
      (node (ref "X1") (pin "18") (pinfunction "GPIO24_18") (pintype "bidirectional"))
    )
    (net (code "24") (name "Net-(IC1-PWM{slash}DP18)") (class "Default")
      (node (ref "IC1") (pin "18") (pinfunction "PWM/DP18_18") (pintype "bidirectional"))
      (node (ref "PAD-DP18") (pin "1") (pinfunction "P_1") (pintype "passive"))
    )
    (net (code "25") (name "Net-(IC1-PWM{slash}DP24)") (class "Default")
      (node (ref "IC1") (pin "24") (pinfunction "PWM/DP24_24") (pintype "bidirectional"))
      (node (ref "X1") (pin "16") (pinfunction "GPIO23_16") (pintype "bidirectional"))
    )
    (net (code "26") (name "Net-(IC1-SERAL_RX{slash}DP15)") (class "Default")
      (node (ref "DRX") (pin "C") (pinfunction "C_C") (pintype "passive"))
      (node (ref "IC1") (pin "15") (pinfunction "SERAL_RX/DP15_15") (pintype "bidirectional"))
      (node (ref "X1") (pin "8") (pinfunction "TXD_8") (pintype "bidirectional"))
    )
    (net (code "27") (name "Net-(IC1-SERIAL_TX{slash}DP16)") (class "Default")
      (node (ref "DTX") (pin "C") (pinfunction "C_C") (pintype "passive"))
      (node (ref "IC1") (pin "16") (pinfunction "SERIAL_TX/DP16_16") (pintype "bidirectional"))
      (node (ref "X1") (pin "10") (pinfunction "RXD_10") (pintype "bidirectional"))
    )
    (net (code "28") (name "Net-(PAD54-P)") (class "Default")
      (node (ref "PAD54") (pin "1") (pinfunction "P_1") (pintype "passive"))
      (node (ref "PAD55") (pin "1") (pinfunction "P_1") (pintype "passive"))
      (node (ref "PAD56") (pin "1") (pinfunction "P_1") (pintype "passive"))
      (node (ref "PAD57") (pin "1") (pinfunction "P_1") (pintype "passive"))
      (node (ref "PAD58") (pin "1") (pinfunction "P_1") (pintype "passive"))
      (node (ref "PAD59") (pin "1") (pinfunction "P_1") (pintype "passive"))
      (node (ref "PAD60") (pin "1") (pinfunction "P_1") (pintype "passive"))
      (node (ref "PAD61") (pin "1") (pinfunction "P_1") (pintype "passive"))
      (node (ref "PAD62") (pin "1") (pinfunction "P_1") (pintype "passive"))
      (node (ref "PAD63") (pin "1") (pinfunction "P_1") (pintype "passive"))
      (node (ref "PAD64") (pin "1") (pinfunction "P_1") (pintype "passive"))
      (node (ref "PAD65") (pin "1") (pinfunction "P_1") (pintype "passive"))
      (node (ref "PAD66") (pin "1") (pinfunction "P_1") (pintype "passive"))
      (node (ref "PAD67") (pin "1") (pinfunction "P_1") (pintype "passive"))
    )
    (net (code "29") (name "Net-(PAD70-P)") (class "Default")
      (node (ref "PAD70") (pin "1") (pinfunction "P_1") (pintype "passive"))
      (node (ref "PAD71") (pin "1") (pinfunction "P_1") (pintype "passive"))
      (node (ref "PAD72") (pin "1") (pinfunction "P_1") (pintype "passive"))
      (node (ref "PAD73") (pin "1") (pinfunction "P_1") (pintype "passive"))
      (node (ref "PAD74") (pin "1") (pinfunction "P_1") (pintype "passive"))
      (node (ref "PAD75") (pin "1") (pinfunction "P_1") (pintype "passive"))
      (node (ref "PAD76") (pin "1") (pinfunction "P_1") (pintype "passive"))
      (node (ref "PAD77") (pin "1") (pinfunction "P_1") (pintype "passive"))
      (node (ref "PAD78") (pin "1") (pinfunction "P_1") (pintype "passive"))
      (node (ref "PAD79") (pin "1") (pinfunction "P_1") (pintype "passive"))
      (node (ref "PAD80") (pin "1") (pinfunction "P_1") (pintype "passive"))
      (node (ref "PAD81") (pin "1") (pinfunction "P_1") (pintype "passive"))
      (node (ref "PAD82") (pin "1") (pinfunction "P_1") (pintype "passive"))
      (node (ref "PAD83") (pin "1") (pinfunction "P_1") (pintype "passive"))
    )
    (net (code "30") (name "Net-(Q1-D)") (class "Default")
      (node (ref "JP1") (pin "4") (pinfunction "4_4") (pintype "passive"))
      (node (ref "Q1") (pin "P$2") (pinfunction "D_P$2") (pintype "passive"))
    )
    (net (code "31") (name "Net-(Q1-G)") (class "Default")
      (node (ref "Q1") (pin "P$1") (pinfunction "G_P$1") (pintype "passive"))
      (node (ref "R1") (pin "1") (pinfunction "1_1") (pintype "passive"))
      (node (ref "R3") (pin "2") (pinfunction "2_2") (pintype "passive"))
    )
    (net (code "32") (name "Net-(T1-B)") (class "Default")
      (node (ref "R2") (pin "2") (pinfunction "2_2") (pintype "passive"))
      (node (ref "R4") (pin "2") (pinfunction "2_2") (pintype "passive"))
      (node (ref "T1") (pin "1") (pinfunction "B_1") (pintype "passive"))
    )
    (net (code "33") (name "Net-(T1-C)") (class "Default")
      (node (ref "R3") (pin "1") (pinfunction "1_1") (pintype "passive"))
      (node (ref "T1") (pin "3") (pinfunction "C_3") (pintype "passive"))
    )
    (net (code "34") (name "Net-(X1-3V3A)") (class "Default")
      (node (ref "JP1") (pin "1") (pinfunction "1_1") (pintype "passive"))
      (node (ref "X1") (pin "1") (pinfunction "3V3A_1") (pintype "power_in"))
      (node (ref "X1") (pin "17") (pinfunction "3V3B_17") (pintype "power_in"))
    )
    (net (code "35") (name "Net-(X1-5V0A)") (class "Default")
      (node (ref "JP1") (pin "3") (pinfunction "3_3") (pintype "passive"))
      (node (ref "X1") (pin "2") (pinfunction "5V0A_2") (pintype "power_in"))
      (node (ref "X1") (pin "4") (pinfunction "5V0B_4") (pintype "power_in"))
    )
    (net (code "36") (name "unconnected-(5V_CENTER+-Pad3)") (class "Default")
      (node (ref "5V_CENTER+") (pin "3") (pinfunction "3_3") (pintype "passive"))
    )
    (net (code "37") (name "unconnected-(IC1-SWCLK-Pad3)") (class "Default")
      (node (ref "IC1") (pin "3") (pinfunction "SWCLK_3") (pintype "bidirectional"))
    )
    (net (code "38") (name "unconnected-(IC1-SWDIO-Pad12)") (class "Default")
      (node (ref "IC1") (pin "12") (pinfunction "SWDIO_12") (pintype "bidirectional"))
    )
    (net (code "39") (name "unconnected-(IC1-XTALIN-Pad20)") (class "Default")
      (node (ref "IC1") (pin "20") (pinfunction "XTALIN_20") (pintype "input"))
    )
    (net (code "40") (name "unconnected-(IC1-XTALOUT-Pad19)") (class "Default")
      (node (ref "IC1") (pin "19") (pinfunction "XTALOUT_19") (pintype "output"))
    )
    (net (code "41") (name "unconnected-(PAD2-P-Pad1)") (class "Default")
      (node (ref "PAD2") (pin "1") (pinfunction "P_1") (pintype "passive"))
    )
    (net (code "42") (name "unconnected-(PAD3-P-Pad1)") (class "Default")
      (node (ref "PAD3") (pin "1") (pinfunction "P_1") (pintype "passive"))
    )
    (net (code "43") (name "unconnected-(PAD4-P-Pad1)") (class "Default")
      (node (ref "PAD4") (pin "1") (pinfunction "P_1") (pintype "passive"))
    )
    (net (code "44") (name "unconnected-(PAD5-P-Pad1)") (class "Default")
      (node (ref "PAD5") (pin "1") (pinfunction "P_1") (pintype "passive"))
    )
    (net (code "45") (name "unconnected-(PAD6-P-Pad1)") (class "Default")
      (node (ref "PAD6") (pin "1") (pinfunction "P_1") (pintype "passive"))
    )
    (net (code "46") (name "unconnected-(PAD7-P-Pad1)") (class "Default")
      (node (ref "PAD7") (pin "1") (pinfunction "P_1") (pintype "passive"))
    )
    (net (code "47") (name "unconnected-(PAD8-P-Pad1)") (class "Default")
      (node (ref "PAD8") (pin "1") (pinfunction "P_1") (pintype "passive"))
    )
    (net (code "48") (name "unconnected-(PAD9-P-Pad1)") (class "Default")
      (node (ref "PAD9") (pin "1") (pinfunction "P_1") (pintype "passive"))
    )
    (net (code "49") (name "unconnected-(PAD11-P-Pad1)") (class "Default")
      (node (ref "PAD11") (pin "1") (pinfunction "P_1") (pintype "passive"))
    )
    (net (code "50") (name "unconnected-(PAD12-P-Pad1)") (class "Default")
      (node (ref "PAD12") (pin "1") (pinfunction "P_1") (pintype "passive"))
    )
    (net (code "51") (name "unconnected-(PAD13-P-Pad1)") (class "Default")
      (node (ref "PAD13") (pin "1") (pinfunction "P_1") (pintype "passive"))
    )
    (net (code "52") (name "unconnected-(PAD14-P-Pad1)") (class "Default")
      (node (ref "PAD14") (pin "1") (pinfunction "P_1") (pintype "passive"))
    )
    (net (code "53") (name "unconnected-(PAD15-P-Pad1)") (class "Default")
      (node (ref "PAD15") (pin "1") (pinfunction "P_1") (pintype "passive"))
    )
    (net (code "54") (name "unconnected-(PAD16-P-Pad1)") (class "Default")
      (node (ref "PAD16") (pin "1") (pinfunction "P_1") (pintype "passive"))
    )
    (net (code "55") (name "unconnected-(PAD17-P-Pad1)") (class "Default")
      (node (ref "PAD17") (pin "1") (pinfunction "P_1") (pintype "passive"))
    )
    (net (code "56") (name "unconnected-(PAD18-P-Pad1)") (class "Default")
      (node (ref "PAD18") (pin "1") (pinfunction "P_1") (pintype "passive"))
    )
    (net (code "57") (name "unconnected-(PAD20-P-Pad1)") (class "Default")
      (node (ref "PAD20") (pin "1") (pinfunction "P_1") (pintype "passive"))
    )
    (net (code "58") (name "unconnected-(PAD21-P-Pad1)") (class "Default")
      (node (ref "PAD21") (pin "1") (pinfunction "P_1") (pintype "passive"))
    )
    (net (code "59") (name "unconnected-(PAD22-P-Pad1)") (class "Default")
      (node (ref "PAD22") (pin "1") (pinfunction "P_1") (pintype "passive"))
    )
    (net (code "60") (name "unconnected-(PAD23-P-Pad1)") (class "Default")
      (node (ref "PAD23") (pin "1") (pinfunction "P_1") (pintype "passive"))
    )
    (net (code "61") (name "unconnected-(PAD24-P-Pad1)") (class "Default")
      (node (ref "PAD24") (pin "1") (pinfunction "P_1") (pintype "passive"))
    )
    (net (code "62") (name "unconnected-(PAD25-P-Pad1)") (class "Default")
      (node (ref "PAD25") (pin "1") (pinfunction "P_1") (pintype "passive"))
    )
    (net (code "63") (name "unconnected-(PAD26-P-Pad1)") (class "Default")
      (node (ref "PAD26") (pin "1") (pinfunction "P_1") (pintype "passive"))
    )
    (net (code "64") (name "unconnected-(PAD27-P-Pad1)") (class "Default")
      (node (ref "PAD27") (pin "1") (pinfunction "P_1") (pintype "passive"))
    )
    (net (code "65") (name "unconnected-(PAD29-P-Pad1)") (class "Default")
      (node (ref "PAD29") (pin "1") (pinfunction "P_1") (pintype "passive"))
    )
    (net (code "66") (name "unconnected-(PAD30-P-Pad1)") (class "Default")
      (node (ref "PAD30") (pin "1") (pinfunction "P_1") (pintype "passive"))
    )
    (net (code "67") (name "unconnected-(PAD31-P-Pad1)") (class "Default")
      (node (ref "PAD31") (pin "1") (pinfunction "P_1") (pintype "passive"))
    )
    (net (code "68") (name "unconnected-(PAD32-P-Pad1)") (class "Default")
      (node (ref "PAD32") (pin "1") (pinfunction "P_1") (pintype "passive"))
    )
    (net (code "69") (name "unconnected-(PAD33-P-Pad1)") (class "Default")
      (node (ref "PAD33") (pin "1") (pinfunction "P_1") (pintype "passive"))
    )
    (net (code "70") (name "unconnected-(PAD34-P-Pad1)") (class "Default")
      (node (ref "PAD34") (pin "1") (pinfunction "P_1") (pintype "passive"))
    )
    (net (code "71") (name "unconnected-(PAD35-P-Pad1)") (class "Default")
      (node (ref "PAD35") (pin "1") (pinfunction "P_1") (pintype "passive"))
    )
    (net (code "72") (name "unconnected-(PAD36-P-Pad1)") (class "Default")
      (node (ref "PAD36") (pin "1") (pinfunction "P_1") (pintype "passive"))
    )
    (net (code "73") (name "unconnected-(PAD38-P-Pad1)") (class "Default")
      (node (ref "PAD38") (pin "1") (pinfunction "P_1") (pintype "passive"))
    )
    (net (code "74") (name "unconnected-(PAD39-P-Pad1)") (class "Default")
      (node (ref "PAD39") (pin "1") (pinfunction "P_1") (pintype "passive"))
    )
    (net (code "75") (name "unconnected-(PAD40-P-Pad1)") (class "Default")
      (node (ref "PAD40") (pin "1") (pinfunction "P_1") (pintype "passive"))
    )
    (net (code "76") (name "unconnected-(PAD41-P-Pad1)") (class "Default")
      (node (ref "PAD41") (pin "1") (pinfunction "P_1") (pintype "passive"))
    )
    (net (code "77") (name "unconnected-(PAD42-P-Pad1)") (class "Default")
      (node (ref "PAD42") (pin "1") (pinfunction "P_1") (pintype "passive"))
    )
    (net (code "78") (name "unconnected-(PAD43-P-Pad1)") (class "Default")
      (node (ref "PAD43") (pin "1") (pinfunction "P_1") (pintype "passive"))
    )
    (net (code "79") (name "unconnected-(PAD44-P-Pad1)") (class "Default")
      (node (ref "PAD44") (pin "1") (pinfunction "P_1") (pintype "passive"))
    )
    (net (code "80") (name "unconnected-(PAD45-P-Pad1)") (class "Default")
      (node (ref "PAD45") (pin "1") (pinfunction "P_1") (pintype "passive"))
    )
    (net (code "81") (name "unconnected-(PAD46-P-Pad1)") (class "Default")
      (node (ref "PAD46") (pin "1") (pinfunction "P_1") (pintype "passive"))
    )
    (net (code "82") (name "unconnected-(PAD47-P-Pad1)") (class "Default")
      (node (ref "PAD47") (pin "1") (pinfunction "P_1") (pintype "passive"))
    )
    (net (code "83") (name "unconnected-(PAD48-P-Pad1)") (class "Default")
      (node (ref "PAD48") (pin "1") (pinfunction "P_1") (pintype "passive"))
    )
    (net (code "84") (name "unconnected-(PAD49-P-Pad1)") (class "Default")
      (node (ref "PAD49") (pin "1") (pinfunction "P_1") (pintype "passive"))
    )
    (net (code "85") (name "unconnected-(PAD50-P-Pad1)") (class "Default")
      (node (ref "PAD50") (pin "1") (pinfunction "P_1") (pintype "passive"))
    )
    (net (code "86") (name "unconnected-(PAD51-P-Pad1)") (class "Default")
      (node (ref "PAD51") (pin "1") (pinfunction "P_1") (pintype "passive"))
    )
    (net (code "87") (name "unconnected-(PAD101-P-Pad1)") (class "Default")
      (node (ref "PAD101") (pin "1") (pinfunction "P_1") (pintype "passive"))
    )
    (net (code "88") (name "unconnected-(PAD102-P-Pad1)") (class "Default")
      (node (ref "PAD102") (pin "1") (pinfunction "P_1") (pintype "passive"))
    )
    (net (code "89") (name "unconnected-(PAD103-P-Pad1)") (class "Default")
      (node (ref "PAD103") (pin "1") (pinfunction "P_1") (pintype "passive"))
    )
    (net (code "90") (name "unconnected-(PAD104-P-Pad1)") (class "Default")
      (node (ref "PAD104") (pin "1") (pinfunction "P_1") (pintype "passive"))
    )
    (net (code "91") (name "unconnected-(PAD105-P-Pad1)") (class "Default")
      (node (ref "PAD105") (pin "1") (pinfunction "P_1") (pintype "passive"))
    )
    (net (code "92") (name "unconnected-(PAD106-P-Pad1)") (class "Default")
      (node (ref "PAD106") (pin "1") (pinfunction "P_1") (pintype "passive"))
    )
    (net (code "93") (name "unconnected-(PAD107-P-Pad1)") (class "Default")
      (node (ref "PAD107") (pin "1") (pinfunction "P_1") (pintype "passive"))
    )
    (net (code "94") (name "unconnected-(PAD108-P-Pad1)") (class "Default")
      (node (ref "PAD108") (pin "1") (pinfunction "P_1") (pintype "passive"))
    )
    (net (code "95") (name "unconnected-(PAD109-P-Pad1)") (class "Default")
      (node (ref "PAD109") (pin "1") (pinfunction "P_1") (pintype "passive"))
    )
    (net (code "96") (name "unconnected-(PAD110-P-Pad1)") (class "Default")
      (node (ref "PAD110") (pin "1") (pinfunction "P_1") (pintype "passive"))
    )
    (net (code "97") (name "unconnected-(PAD112-P-Pad1)") (class "Default")
      (node (ref "PAD112") (pin "1") (pinfunction "P_1") (pintype "passive"))
    )
    (net (code "98") (name "unconnected-(PAD113-P-Pad1)") (class "Default")
      (node (ref "PAD113") (pin "1") (pinfunction "P_1") (pintype "passive"))
    )
    (net (code "99") (name "unconnected-(PAD114-P-Pad1)") (class "Default")
      (node (ref "PAD114") (pin "1") (pinfunction "P_1") (pintype "passive"))
    )
    (net (code "100") (name "unconnected-(PAD115-P-Pad1)") (class "Default")
      (node (ref "PAD115") (pin "1") (pinfunction "P_1") (pintype "passive"))
    )
    (net (code "101") (name "unconnected-(PAD126-P-Pad1)") (class "Default")
      (node (ref "PAD126") (pin "1") (pinfunction "P_1") (pintype "passive"))
    )
    (net (code "102") (name "unconnected-(PAD127-P-Pad1)") (class "Default")
      (node (ref "PAD127") (pin "1") (pinfunction "P_1") (pintype "passive"))
    )
    (net (code "103") (name "unconnected-(PAD128-P-Pad1)") (class "Default")
      (node (ref "PAD128") (pin "1") (pinfunction "P_1") (pintype "passive"))
    )
    (net (code "104") (name "unconnected-(PAD129-P-Pad1)") (class "Default")
      (node (ref "PAD129") (pin "1") (pinfunction "P_1") (pintype "passive"))
    )
    (net (code "105") (name "unconnected-(PAD130-P-Pad1)") (class "Default")
      (node (ref "PAD130") (pin "1") (pinfunction "P_1") (pintype "passive"))
    )
    (net (code "106") (name "unconnected-(PAD131-P-Pad1)") (class "Default")
      (node (ref "PAD131") (pin "1") (pinfunction "P_1") (pintype "passive"))
    )
    (net (code "107") (name "unconnected-(PAD133-P-Pad1)") (class "Default")
      (node (ref "PAD133") (pin "1") (pinfunction "P_1") (pintype "passive"))
    )
    (net (code "108") (name "unconnected-(PAD134-P-Pad1)") (class "Default")
      (node (ref "PAD134") (pin "1") (pinfunction "P_1") (pintype "passive"))
    )
    (net (code "109") (name "unconnected-(PAD135-P-Pad1)") (class "Default")
      (node (ref "PAD135") (pin "1") (pinfunction "P_1") (pintype "passive"))
    )
    (net (code "110") (name "unconnected-(PAD136-P-Pad1)") (class "Default")
      (node (ref "PAD136") (pin "1") (pinfunction "P_1") (pintype "passive"))
    )
    (net (code "111") (name "unconnected-(PAD137-P-Pad1)") (class "Default")
      (node (ref "PAD137") (pin "1") (pinfunction "P_1") (pintype "passive"))
    )
    (net (code "112") (name "unconnected-(PAD138-P-Pad1)") (class "Default")
      (node (ref "PAD138") (pin "1") (pinfunction "P_1") (pintype "passive"))
    )
    (net (code "113") (name "unconnected-(PAD140-P-Pad1)") (class "Default")
      (node (ref "PAD140") (pin "1") (pinfunction "P_1") (pintype "passive"))
    )
    (net (code "114") (name "unconnected-(PAD141-P-Pad1)") (class "Default")
      (node (ref "PAD141") (pin "1") (pinfunction "P_1") (pintype "passive"))
    )
    (net (code "115") (name "unconnected-(PAD142-P-Pad1)") (class "Default")
      (node (ref "PAD142") (pin "1") (pinfunction "P_1") (pintype "passive"))
    )
    (net (code "116") (name "unconnected-(PAD143-P-Pad1)") (class "Default")
      (node (ref "PAD143") (pin "1") (pinfunction "P_1") (pintype "passive"))
    )
    (net (code "117") (name "unconnected-(PAD144-P-Pad1)") (class "Default")
      (node (ref "PAD144") (pin "1") (pinfunction "P_1") (pintype "passive"))
    )
    (net (code "118") (name "unconnected-(PAD145-P-Pad1)") (class "Default")
      (node (ref "PAD145") (pin "1") (pinfunction "P_1") (pintype "passive"))
    )
    (net (code "119") (name "unconnected-(PAD147-P-Pad1)") (class "Default")
      (node (ref "PAD147") (pin "1") (pinfunction "P_1") (pintype "passive"))
    )
    (net (code "120") (name "unconnected-(PAD148-P-Pad1)") (class "Default")
      (node (ref "PAD148") (pin "1") (pinfunction "P_1") (pintype "passive"))
    )
    (net (code "121") (name "unconnected-(PAD149-P-Pad1)") (class "Default")
      (node (ref "PAD149") (pin "1") (pinfunction "P_1") (pintype "passive"))
    )
    (net (code "122") (name "unconnected-(PAD150-P-Pad1)") (class "Default")
      (node (ref "PAD150") (pin "1") (pinfunction "P_1") (pintype "passive"))
    )
    (net (code "123") (name "unconnected-(PAD151-P-Pad1)") (class "Default")
      (node (ref "PAD151") (pin "1") (pinfunction "P_1") (pintype "passive"))
    )
    (net (code "124") (name "unconnected-(PAD152-P-Pad1)") (class "Default")
      (node (ref "PAD152") (pin "1") (pinfunction "P_1") (pintype "passive"))
    )
    (net (code "125") (name "unconnected-(X1-GPIO04-Pad7)") (class "Default")
      (node (ref "X1") (pin "7") (pinfunction "GPIO04_7") (pintype "bidirectional"))
    )
    (net (code "126") (name "unconnected-(X1-GPIO05-Pad29)") (class "Default")
      (node (ref "X1") (pin "29") (pinfunction "GPIO05_29") (pintype "no_connect"))
    )
    (net (code "127") (name "unconnected-(X1-GPIO06-Pad31)") (class "Default")
      (node (ref "X1") (pin "31") (pinfunction "GPIO06_31") (pintype "no_connect"))
    )
    (net (code "128") (name "unconnected-(X1-GPIO12-Pad32)") (class "Default")
      (node (ref "X1") (pin "32") (pinfunction "GPIO12_32") (pintype "no_connect"))
    )
    (net (code "129") (name "unconnected-(X1-GPIO13-Pad33)") (class "Default")
      (node (ref "X1") (pin "33") (pinfunction "GPIO13_33") (pintype "no_connect"))
    )
    (net (code "130") (name "unconnected-(X1-GPIO16-Pad36)") (class "Default")
      (node (ref "X1") (pin "36") (pinfunction "GPIO16_36") (pintype "no_connect"))
    )
    (net (code "131") (name "unconnected-(X1-GPIO17-Pad11)") (class "Default")
      (node (ref "X1") (pin "11") (pinfunction "GPIO17_11") (pintype "bidirectional"))
    )
    (net (code "132") (name "unconnected-(X1-GPIO18-Pad12)") (class "Default")
      (node (ref "X1") (pin "12") (pinfunction "GPIO18_12") (pintype "bidirectional"))
    )
    (net (code "133") (name "unconnected-(X1-GPIO19-Pad35)") (class "Default")
      (node (ref "X1") (pin "35") (pinfunction "GPIO19_35") (pintype "no_connect"))
    )
    (net (code "134") (name "unconnected-(X1-GPIO20-Pad38)") (class "Default")
      (node (ref "X1") (pin "38") (pinfunction "GPIO20_38") (pintype "no_connect"))
    )
    (net (code "135") (name "unconnected-(X1-GPIO21-Pad40)") (class "Default")
      (node (ref "X1") (pin "40") (pinfunction "GPIO21_40") (pintype "no_connect"))
    )
    (net (code "136") (name "unconnected-(X1-GPIO22-Pad15)") (class "Default")
      (node (ref "X1") (pin "15") (pinfunction "GPIO22_15") (pintype "bidirectional"))
    )
    (net (code "137") (name "unconnected-(X1-GPIO25-Pad22)") (class "Default")
      (node (ref "X1") (pin "22") (pinfunction "GPIO25_22") (pintype "bidirectional"))
    )
    (net (code "138") (name "unconnected-(X1-GPIO26-Pad37)") (class "Default")
      (node (ref "X1") (pin "37") (pinfunction "GPIO26_37") (pintype "no_connect"))
    )
    (net (code "139") (name "unconnected-(X1-GPIO27-Pad13)") (class "Default")
      (node (ref "X1") (pin "13") (pinfunction "GPIO27_13") (pintype "bidirectional"))
    )
    (net (code "140") (name "unconnected-(X1-ID_SC-Pad28)") (class "Default")
      (node (ref "X1") (pin "28") (pinfunction "ID_SC_28") (pintype "no_connect"))
    )
    (net (code "141") (name "unconnected-(X1-ID_SD-Pad27)") (class "Default")
      (node (ref "X1") (pin "27") (pinfunction "ID_SD_27") (pintype "no_connect"))
    )
    (net (code "142") (name "unconnected-(X1-SPI_CE0-Pad24)") (class "Default")
      (node (ref "X1") (pin "24") (pinfunction "SPI_CE0_24") (pintype "bidirectional"))
    )
    (net (code "143") (name "unconnected-(X1-SPI_CE1-Pad26)") (class "Default")
      (node (ref "X1") (pin "26") (pinfunction "SPI_CE1_26") (pintype "bidirectional"))
    )
    (net (code "144") (name "unconnected-(X1-SPI_MISO-Pad21)") (class "Default")
      (node (ref "X1") (pin "21") (pinfunction "SPI_MISO_21") (pintype "bidirectional"))
    )
    (net (code "145") (name "unconnected-(X1-SPI_MOSI-Pad19)") (class "Default")
      (node (ref "X1") (pin "19") (pinfunction "SPI_MOSI_19") (pintype "bidirectional"))
    )
    (net (code "146") (name "unconnected-(X1-SPI_SCLK-Pad23)") (class "Default")
      (node (ref "X1") (pin "23") (pinfunction "SPI_SCLK_23") (pintype "bidirectional"))
    )
  )
)
